# Locomotion_Breakout.net
KiCad netlist of a schematic drawn in EAGLE
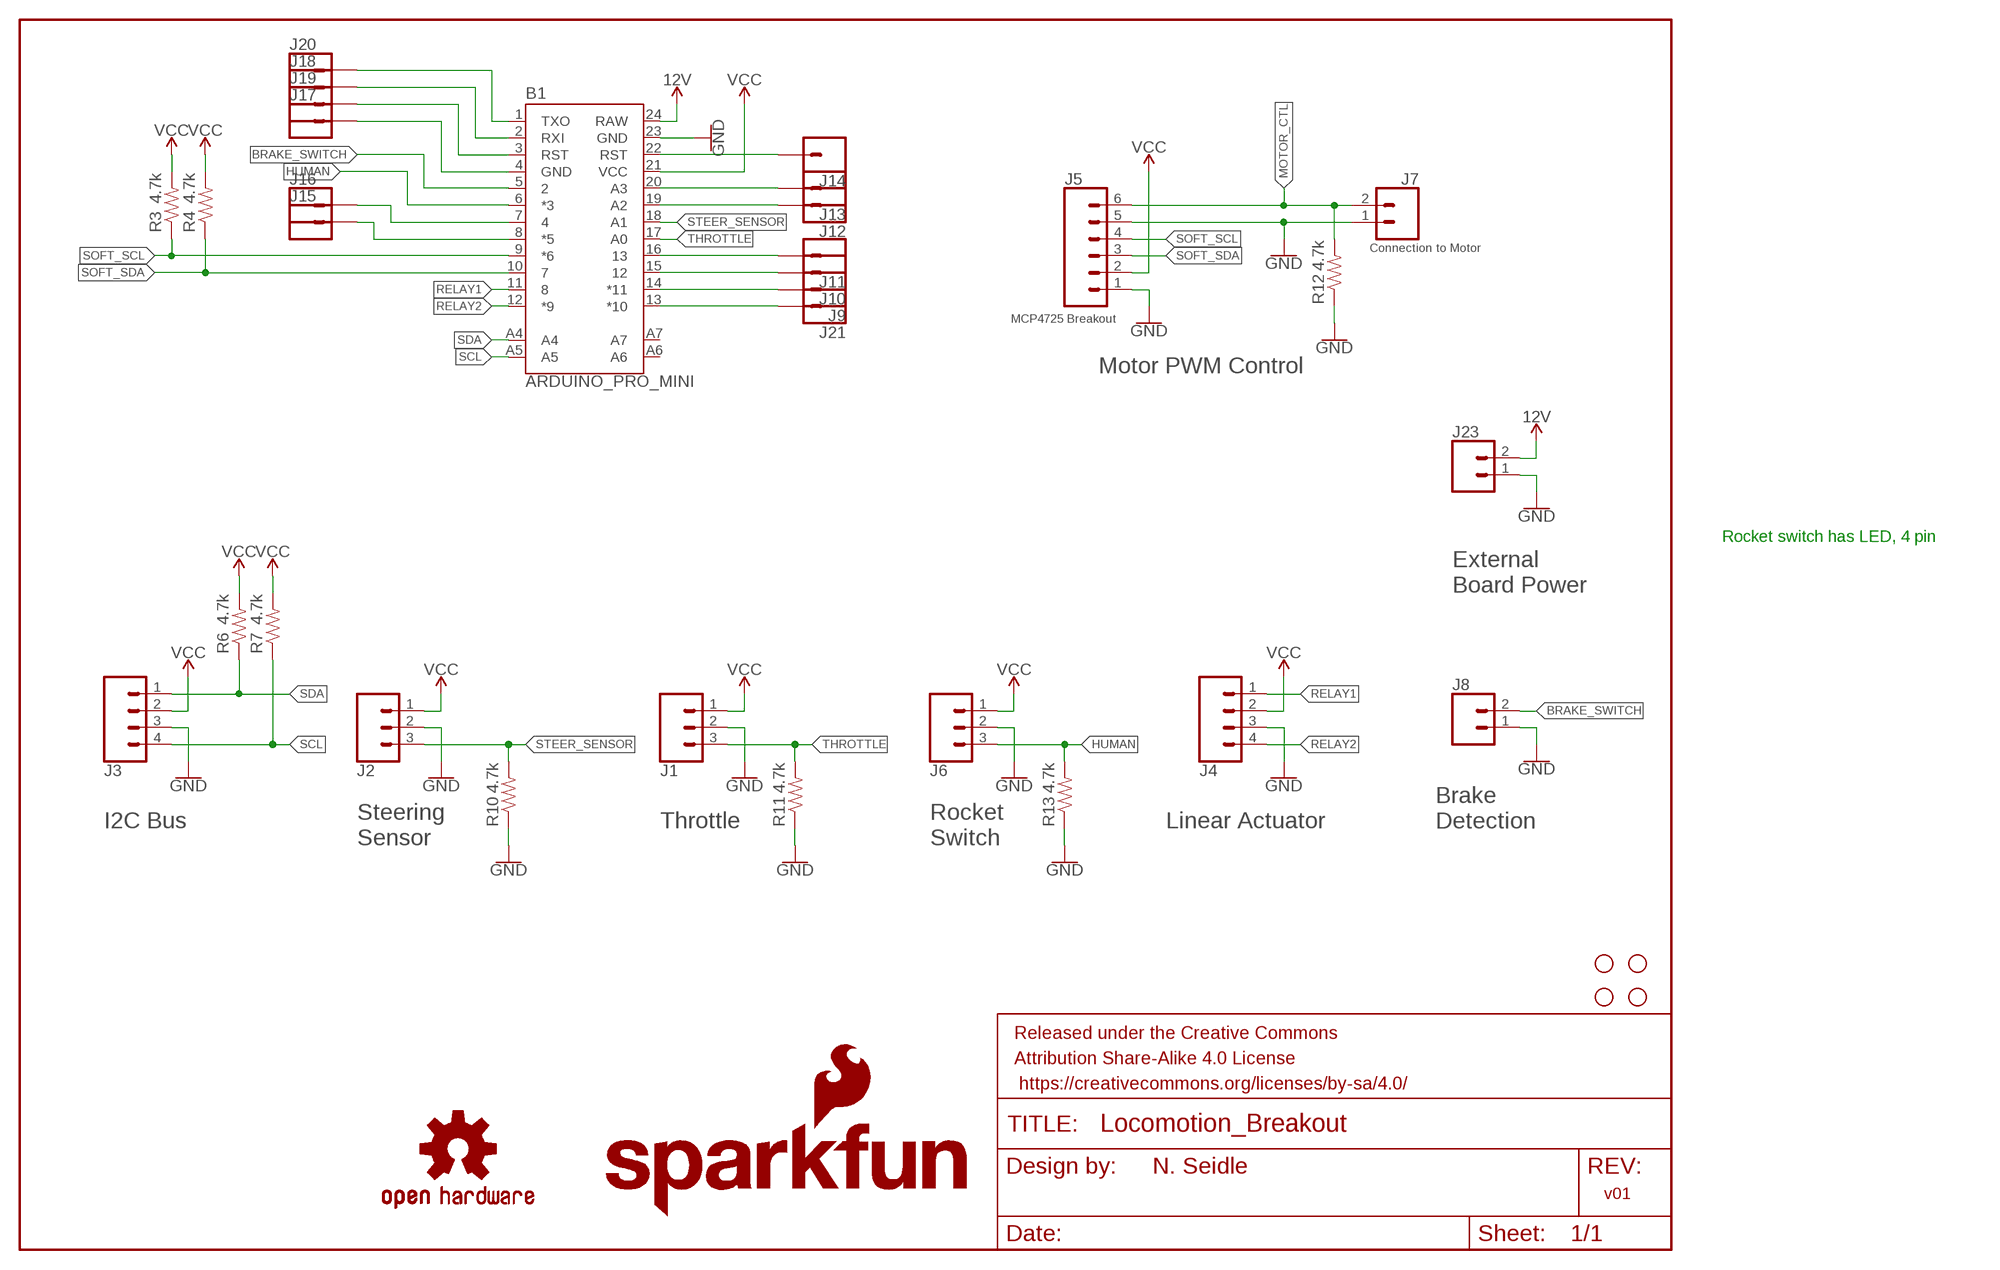
[diagram p0: schematic, sheet 1]

(export (version "E")
  (design (tool "Eeschema 10.0.6"))
  (components
    (comp (ref "B1")
      (value "ARDUINO_PRO_MINI")
      (footprint "eagle-import:ARDUINO_PRO_MINI")
      (libsource (lib "eagle-import") (part "ARDUINO_PRO_MINI"))
    )
    (comp (ref "FRAME1")
      (value "FRAME-LETTER")
      (footprint "eagle-import:CREATIVE_COMMONS")
      (libsource (lib "eagle-import") (part "FRAME-LETTER"))
    )
    (comp (ref "J1")
      (value "CONN_03JST-PTH-VERT")
      (footprint "eagle-import:JST-3-PTH-VERT")
      (libsource (lib "eagle-import") (part "CONN_03JST-PTH-VERT"))
    )
    (comp (ref "J2")
      (value "CONN_03JST-PTH-VERT")
      (footprint "eagle-import:JST-3-PTH-VERT")
      (libsource (lib "eagle-import") (part "CONN_03JST-PTH-VERT"))
    )
    (comp (ref "J3")
      (value "CONN_04JST-PTH-VERT")
      (footprint "eagle-import:JST-4-PTH-VERT")
      (libsource (lib "eagle-import") (part "CONN_04JST-PTH-VERT"))
    )
    (comp (ref "J4")
      (value "CONN_04JST-PTH-VERT")
      (footprint "eagle-import:JST-4-PTH-VERT")
      (libsource (lib "eagle-import") (part "CONN_04JST-PTH-VERT"))
    )
    (comp (ref "J5")
      (value "CONN_06SILK_FEMALE_PTH")
      (footprint "eagle-import:1X06")
      (libsource (lib "eagle-import") (part "CONN_06SILK_FEMALE_PTH"))
    )
    (comp (ref "J6")
      (value "CONN_03JST-PTH-VERT")
      (footprint "eagle-import:JST-3-PTH-VERT")
      (libsource (lib "eagle-import") (part "CONN_03JST-PTH-VERT"))
    )
    (comp (ref "J7")
      (value "CONN_02JST-PTH-VERT")
      (footprint "eagle-import:JST-2-PTH-VERT")
      (libsource (lib "eagle-import") (part "CONN_02JST-PTH-VERT"))
    )
    (comp (ref "J8")
      (value "CONN_02JST-PTH-VERT")
      (footprint "eagle-import:JST-2-PTH-VERT")
      (libsource (lib "eagle-import") (part "CONN_02JST-PTH-VERT"))
    )
    (comp (ref "J9")
      (value "CONN_01PTH_NO_SILK_YES_STOP")
      (footprint "eagle-import:1X01_NO_SILK")
      (libsource (lib "eagle-import") (part "CONN_01PTH_NO_SILK_YES_STOP"))
    )
    (comp (ref "J10")
      (value "CONN_01PTH_NO_SILK_YES_STOP")
      (footprint "eagle-import:1X01_NO_SILK")
      (libsource (lib "eagle-import") (part "CONN_01PTH_NO_SILK_YES_STOP"))
    )
    (comp (ref "J11")
      (value "CONN_01PTH_NO_SILK_YES_STOP")
      (footprint "eagle-import:1X01_NO_SILK")
      (libsource (lib "eagle-import") (part "CONN_01PTH_NO_SILK_YES_STOP"))
    )
    (comp (ref "J12")
      (value "CONN_01PTH_NO_SILK_YES_STOP")
      (footprint "eagle-import:1X01_NO_SILK")
      (libsource (lib "eagle-import") (part "CONN_01PTH_NO_SILK_YES_STOP"))
    )
    (comp (ref "J13")
      (value "CONN_01PTH_NO_SILK_YES_STOP")
      (footprint "eagle-import:1X01_NO_SILK")
      (libsource (lib "eagle-import") (part "CONN_01PTH_NO_SILK_YES_STOP"))
    )
    (comp (ref "J14")
      (value "CONN_01PTH_NO_SILK_YES_STOP")
      (footprint "eagle-import:1X01_NO_SILK")
      (libsource (lib "eagle-import") (part "CONN_01PTH_NO_SILK_YES_STOP"))
    )
    (comp (ref "J15")
      (value "CONN_01PTH_NO_SILK_YES_STOP")
      (footprint "eagle-import:1X01_NO_SILK")
      (libsource (lib "eagle-import") (part "CONN_01PTH_NO_SILK_YES_STOP"))
    )
    (comp (ref "J16")
      (value "CONN_01PTH_NO_SILK_YES_STOP")
      (footprint "eagle-import:1X01_NO_SILK")
      (libsource (lib "eagle-import") (part "CONN_01PTH_NO_SILK_YES_STOP"))
    )
    (comp (ref "J17")
      (value "CONN_01PTH_NO_SILK_YES_STOP")
      (footprint "eagle-import:1X01_NO_SILK")
      (libsource (lib "eagle-import") (part "CONN_01PTH_NO_SILK_YES_STOP"))
    )
    (comp (ref "J18")
      (value "CONN_01PTH_NO_SILK_YES_STOP")
      (footprint "eagle-import:1X01_NO_SILK")
      (libsource (lib "eagle-import") (part "CONN_01PTH_NO_SILK_YES_STOP"))
    )
    (comp (ref "J19")
      (value "CONN_01PTH_NO_SILK_YES_STOP")
      (footprint "eagle-import:1X01_NO_SILK")
      (libsource (lib "eagle-import") (part "CONN_01PTH_NO_SILK_YES_STOP"))
    )
    (comp (ref "J20")
      (value "CONN_01PTH_NO_SILK_YES_STOP")
      (footprint "eagle-import:1X01_NO_SILK")
      (libsource (lib "eagle-import") (part "CONN_01PTH_NO_SILK_YES_STOP"))
    )
    (comp (ref "J21")
      (value "CONN_01PTH_NO_SILK_YES_STOP")
      (footprint "eagle-import:1X01_NO_SILK")
      (libsource (lib "eagle-import") (part "CONN_01PTH_NO_SILK_YES_STOP"))
    )
    (comp (ref "J23")
      (value "CONN_02JST-PTH-VERT")
      (footprint "eagle-import:JST-2-PTH-VERT")
      (libsource (lib "eagle-import") (part "CONN_02JST-PTH-VERT"))
    )
    (comp (ref "LOGO1")
      (value "SFE_LOGO_FLAME.1_INCH")
      (footprint "eagle-import:SFE_LOGO_FLAME_.1")
      (libsource (lib "eagle-import") (part "SFE_LOGO_FLAME.1_INCH"))
    )
    (comp (ref "LOGO2")
      (value "OSHW-LOGOS")
      (footprint "eagle-import:OSHW-LOGO-S")
      (libsource (lib "eagle-import") (part "OSHW-LOGOS"))
    )
    (comp (ref "LOGO3")
      (value "SFE_LOGO_NAME.1_INCH")
      (footprint "eagle-import:SFE_LOGO_NAME_.1")
      (libsource (lib "eagle-import") (part "SFE_LOGO_NAME.1_INCH"))
    )
    (comp (ref "R3")
      (value "4.7k")
      (footprint "eagle-import:AXIAL-0.3")
      (libsource (lib "eagle-import") (part "1KOHM-HORIZ-1/4W-5%"))
    )
    (comp (ref "R4")
      (value "4.7k")
      (footprint "eagle-import:AXIAL-0.3")
      (libsource (lib "eagle-import") (part "1KOHM-HORIZ-1/4W-5%"))
    )
    (comp (ref "R6")
      (value "4.7k")
      (footprint "eagle-import:AXIAL-0.3")
      (libsource (lib "eagle-import") (part "1KOHM-HORIZ-1/4W-5%"))
    )
    (comp (ref "R7")
      (value "4.7k")
      (footprint "eagle-import:AXIAL-0.3")
      (libsource (lib "eagle-import") (part "1KOHM-HORIZ-1/4W-5%"))
    )
    (comp (ref "R10")
      (value "4.7k")
      (footprint "eagle-import:AXIAL-0.3")
      (libsource (lib "eagle-import") (part "1KOHM-HORIZ-1/4W-5%"))
    )
    (comp (ref "R11")
      (value "4.7k")
      (footprint "eagle-import:AXIAL-0.3")
      (libsource (lib "eagle-import") (part "1KOHM-HORIZ-1/4W-5%"))
    )
    (comp (ref "R12")
      (value "4.7k")
      (footprint "eagle-import:AXIAL-0.3")
      (libsource (lib "eagle-import") (part "1KOHM-HORIZ-1/4W-5%"))
    )
    (comp (ref "R13")
      (value "4.7k")
      (footprint "eagle-import:AXIAL-0.3")
      (libsource (lib "eagle-import") (part "1KOHM-HORIZ-1/4W-5%"))
    )
    (comp (ref "STANDOFF1")
      (value "STAND-OFF")
      (footprint "eagle-import:STAND-OFF")
      (libsource (lib "eagle-import") (part "STAND-OFF"))
    )
    (comp (ref "STANDOFF2")
      (value "STAND-OFF")
      (footprint "eagle-import:STAND-OFF")
      (libsource (lib "eagle-import") (part "STAND-OFF"))
    )
    (comp (ref "STANDOFF3")
      (value "STAND-OFF")
      (footprint "eagle-import:STAND-OFF")
      (libsource (lib "eagle-import") (part "STAND-OFF"))
    )
    (comp (ref "STANDOFF4")
      (value "STAND-OFF")
      (footprint "eagle-import:STAND-OFF")
      (libsource (lib "eagle-import") (part "STAND-OFF"))
    )
  )
  (nets
    (net (code "1") (name "12V") (class "Default")
      (node (ref "B1") (pin "24") (pinfunction "RAW_24") (pintype "power_in"))
      (node (ref "J23") (pin "2") (pinfunction "2_2") (pintype "passive"))
    )
    (net (code "2") (name "BRAKE_SWITCH") (class "Default")
      (node (ref "B1") (pin "5") (pinfunction "2_5") (pintype "bidirectional"))
      (node (ref "J8") (pin "2") (pinfunction "2_2") (pintype "passive"))
    )
    (net (code "3") (name "GND") (class "Default")
      (node (ref "B1") (pin "23") (pinfunction "GND_23") (pintype "power_in"))
      (node (ref "J1") (pin "2") (pinfunction "2_2") (pintype "passive"))
      (node (ref "J2") (pin "2") (pinfunction "2_2") (pintype "passive"))
      (node (ref "J23") (pin "1") (pinfunction "1_1") (pintype "passive"))
      (node (ref "J3") (pin "3") (pinfunction "3_3") (pintype "passive"))
      (node (ref "J4") (pin "3") (pinfunction "3_3") (pintype "passive"))
      (node (ref "J5") (pin "1") (pinfunction "1_1") (pintype "passive"))
      (node (ref "J5") (pin "5") (pinfunction "5_5") (pintype "passive"))
      (node (ref "J6") (pin "2") (pinfunction "2_2") (pintype "passive"))
      (node (ref "J7") (pin "1") (pinfunction "1_1") (pintype "passive"))
      (node (ref "J8") (pin "1") (pinfunction "1_1") (pintype "passive"))
      (node (ref "R10") (pin "P$1") (pinfunction "1_P$1") (pintype "passive"))
      (node (ref "R11") (pin "P$1") (pinfunction "1_P$1") (pintype "passive"))
      (node (ref "R12") (pin "P$1") (pinfunction "1_P$1") (pintype "passive"))
      (node (ref "R13") (pin "P$1") (pinfunction "1_P$1") (pintype "passive"))
    )
    (net (code "4") (name "HUMAN") (class "Default")
      (node (ref "B1") (pin "6") (pinfunction "*3_6") (pintype "bidirectional"))
      (node (ref "J6") (pin "3") (pinfunction "3_3") (pintype "passive"))
      (node (ref "R13") (pin "P$2") (pinfunction "2_P$2") (pintype "passive"))
    )
    (net (code "5") (name "MOTOR_CTL") (class "Default")
      (node (ref "J5") (pin "6") (pinfunction "6_6") (pintype "passive"))
      (node (ref "J7") (pin "2") (pinfunction "2_2") (pintype "passive"))
      (node (ref "R12") (pin "P$2") (pinfunction "2_P$2") (pintype "passive"))
    )
    (net (code "6") (name "Net-(B1-*5)") (class "Default")
      (node (ref "B1") (pin "8") (pinfunction "*5_8") (pintype "bidirectional"))
      (node (ref "J15") (pin "1") (pinfunction "1_1") (pintype "passive"))
    )
    (net (code "7") (name "Net-(B1-*10)") (class "Default")
      (node (ref "B1") (pin "13") (pinfunction "*10_13") (pintype "bidirectional"))
      (node (ref "J21") (pin "1") (pinfunction "1_1") (pintype "passive"))
    )
    (net (code "8") (name "Net-(B1-*11)") (class "Default")
      (node (ref "B1") (pin "14") (pinfunction "*11_14") (pintype "bidirectional"))
      (node (ref "J9") (pin "1") (pinfunction "1_1") (pintype "passive"))
    )
    (net (code "9") (name "Net-(B1-4)") (class "Default")
      (node (ref "B1") (pin "7") (pinfunction "4_7") (pintype "bidirectional"))
      (node (ref "J16") (pin "1") (pinfunction "1_1") (pintype "passive"))
    )
    (net (code "10") (name "Net-(B1-12)") (class "Default")
      (node (ref "B1") (pin "15") (pinfunction "12_15") (pintype "bidirectional"))
      (node (ref "J10") (pin "1") (pinfunction "1_1") (pintype "passive"))
    )
    (net (code "11") (name "Net-(B1-13)") (class "Default")
      (node (ref "B1") (pin "16") (pinfunction "13_16") (pintype "bidirectional"))
      (node (ref "J11") (pin "1") (pinfunction "1_1") (pintype "passive"))
    )
    (net (code "12") (name "Net-(B1-A2)") (class "Default")
      (node (ref "B1") (pin "19") (pinfunction "A2_19") (pintype "bidirectional"))
      (node (ref "J12") (pin "1") (pinfunction "1_1") (pintype "passive"))
    )
    (net (code "13") (name "Net-(B1-A3)") (class "Default")
      (node (ref "B1") (pin "20") (pinfunction "A3_20") (pintype "bidirectional"))
      (node (ref "J13") (pin "1") (pinfunction "1_1") (pintype "passive"))
    )
    (net (code "14") (name "Net-(B1-GND-Pad4)") (class "Default")
      (node (ref "B1") (pin "4") (pinfunction "GND_4") (pintype "power_in"))
      (node (ref "J17") (pin "1") (pinfunction "1_1") (pintype "passive"))
    )
    (net (code "15") (name "Net-(B1-RST-Pad3)") (class "Default")
      (node (ref "B1") (pin "3") (pinfunction "RST_3") (pintype "bidirectional"))
      (node (ref "J19") (pin "1") (pinfunction "1_1") (pintype "passive"))
    )
    (net (code "16") (name "Net-(B1-RST-Pad22)") (class "Default")
      (node (ref "B1") (pin "22") (pinfunction "RST_22") (pintype "bidirectional"))
      (node (ref "J14") (pin "1") (pinfunction "1_1") (pintype "passive"))
    )
    (net (code "17") (name "Net-(B1-RXI)") (class "Default")
      (node (ref "B1") (pin "2") (pinfunction "RXI_2") (pintype "bidirectional"))
      (node (ref "J18") (pin "1") (pinfunction "1_1") (pintype "passive"))
    )
    (net (code "18") (name "Net-(B1-TXO)") (class "Default")
      (node (ref "B1") (pin "1") (pinfunction "TXO_1") (pintype "bidirectional"))
      (node (ref "J20") (pin "1") (pinfunction "1_1") (pintype "passive"))
    )
    (net (code "19") (name "RELAY1") (class "Default")
      (node (ref "B1") (pin "11") (pinfunction "8_11") (pintype "bidirectional"))
      (node (ref "J4") (pin "1") (pinfunction "1_1") (pintype "passive"))
    )
    (net (code "20") (name "RELAY2") (class "Default")
      (node (ref "B1") (pin "12") (pinfunction "*9_12") (pintype "bidirectional"))
      (node (ref "J4") (pin "4") (pinfunction "4_4") (pintype "passive"))
    )
    (net (code "21") (name "SCL") (class "Default")
      (node (ref "B1") (pin "A5") (pinfunction "A5_A5") (pintype "bidirectional"))
      (node (ref "J3") (pin "4") (pinfunction "4_4") (pintype "passive"))
      (node (ref "R7") (pin "P$1") (pinfunction "1_P$1") (pintype "passive"))
    )
    (net (code "22") (name "SDA") (class "Default")
      (node (ref "B1") (pin "A4") (pinfunction "A4_A4") (pintype "bidirectional"))
      (node (ref "J3") (pin "1") (pinfunction "1_1") (pintype "passive"))
      (node (ref "R6") (pin "P$1") (pinfunction "1_P$1") (pintype "passive"))
    )
    (net (code "23") (name "SOFT_SCL") (class "Default")
      (node (ref "B1") (pin "9") (pinfunction "*6_9") (pintype "bidirectional"))
      (node (ref "J5") (pin "4") (pinfunction "4_4") (pintype "passive"))
      (node (ref "R3") (pin "P$1") (pinfunction "1_P$1") (pintype "passive"))
    )
    (net (code "24") (name "SOFT_SDA") (class "Default")
      (node (ref "B1") (pin "10") (pinfunction "7_10") (pintype "bidirectional"))
      (node (ref "J5") (pin "3") (pinfunction "3_3") (pintype "passive"))
      (node (ref "R4") (pin "P$1") (pinfunction "1_P$1") (pintype "passive"))
    )
    (net (code "25") (name "STEER_SENSOR") (class "Default")
      (node (ref "B1") (pin "18") (pinfunction "A1_18") (pintype "bidirectional"))
      (node (ref "J2") (pin "3") (pinfunction "3_3") (pintype "passive"))
      (node (ref "R10") (pin "P$2") (pinfunction "2_P$2") (pintype "passive"))
    )
    (net (code "26") (name "THROTTLE") (class "Default")
      (node (ref "B1") (pin "17") (pinfunction "A0_17") (pintype "bidirectional"))
      (node (ref "J1") (pin "3") (pinfunction "3_3") (pintype "passive"))
      (node (ref "R11") (pin "P$2") (pinfunction "2_P$2") (pintype "passive"))
    )
    (net (code "27") (name "VCC") (class "Default")
      (node (ref "B1") (pin "21") (pinfunction "VCC_21") (pintype "power_in"))
      (node (ref "J1") (pin "1") (pinfunction "1_1") (pintype "passive"))
      (node (ref "J2") (pin "1") (pinfunction "1_1") (pintype "passive"))
      (node (ref "J3") (pin "2") (pinfunction "2_2") (pintype "passive"))
      (node (ref "J4") (pin "2") (pinfunction "2_2") (pintype "passive"))
      (node (ref "J5") (pin "2") (pinfunction "2_2") (pintype "passive"))
      (node (ref "J6") (pin "1") (pinfunction "1_1") (pintype "passive"))
      (node (ref "R3") (pin "P$2") (pinfunction "2_P$2") (pintype "passive"))
      (node (ref "R4") (pin "P$2") (pinfunction "2_P$2") (pintype "passive"))
      (node (ref "R6") (pin "P$2") (pinfunction "2_P$2") (pintype "passive"))
      (node (ref "R7") (pin "P$2") (pinfunction "2_P$2") (pintype "passive"))
    )
    (net (code "28") (name "unconnected-(B1-PadA6)") (class "Default")
      (node (ref "B1") (pin "A6") (pinfunction "A6_A6") (pintype "bidirectional"))
    )
    (net (code "29") (name "unconnected-(B1-PadA7)") (class "Default")
      (node (ref "B1") (pin "A7") (pinfunction "A7_A7") (pintype "bidirectional"))
    )
  )
)
